# tinyusbboard_tht_singlesided.net
KiCad netlist of a schematic drawn in EAGLE
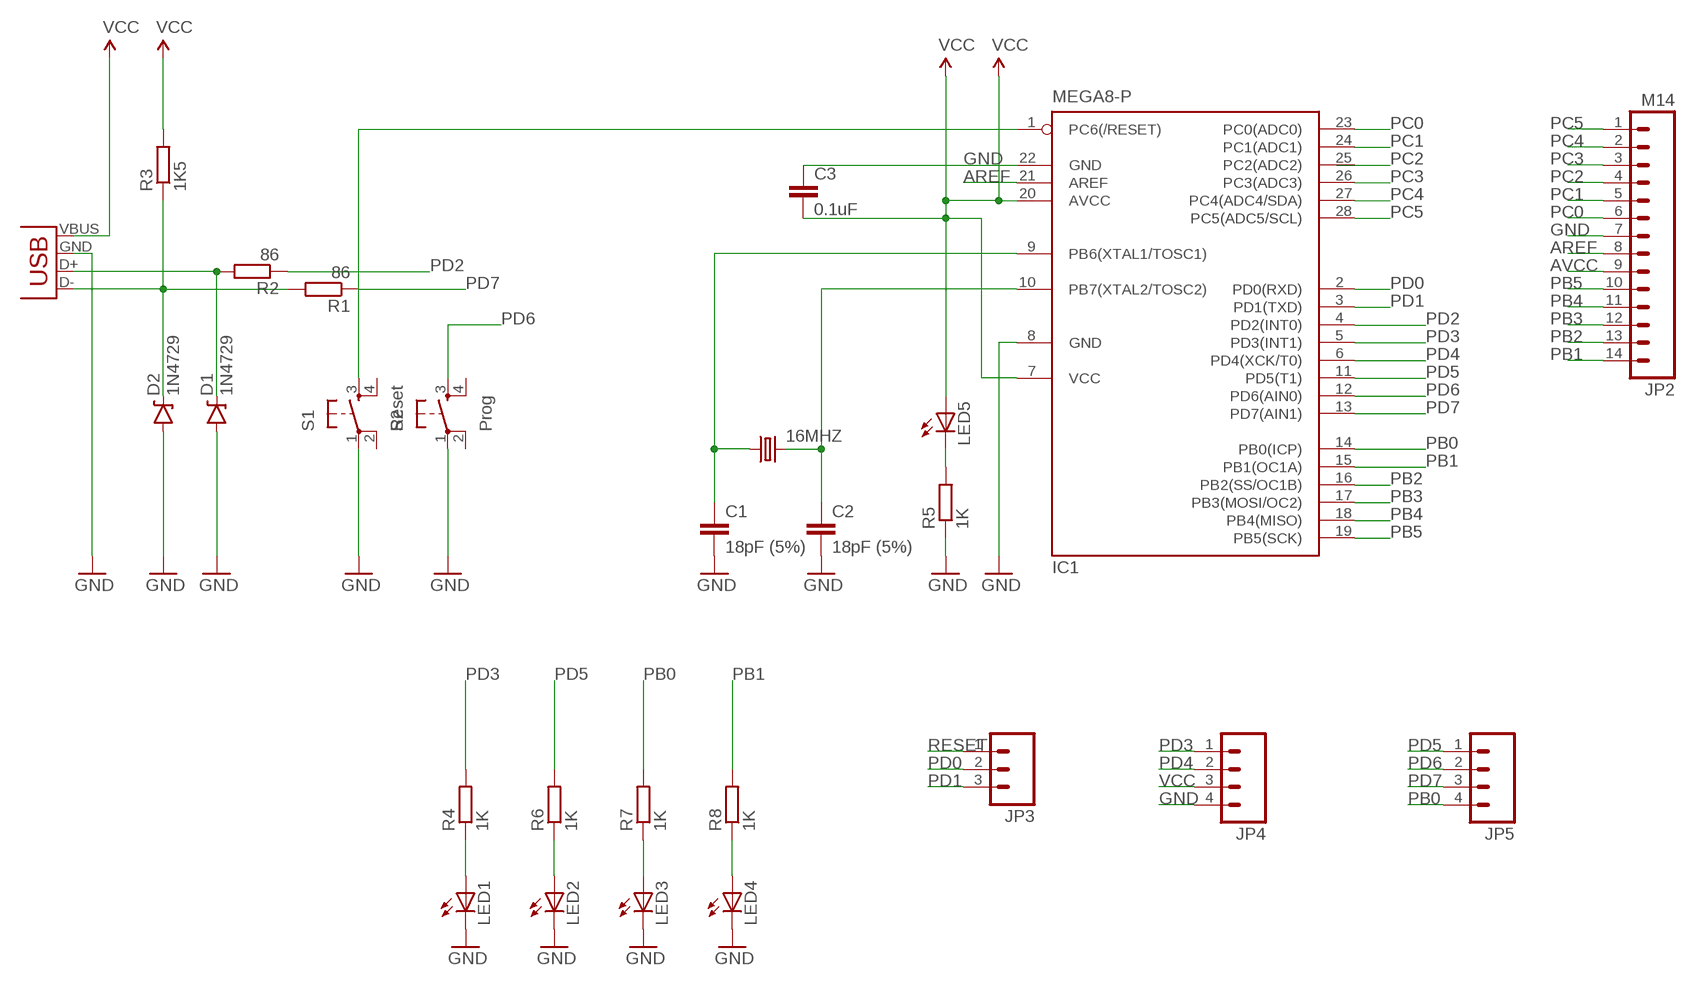
[diagram p0: schematic, sheet 1]

(export (version "E")
  (design (tool "Eeschema 10.0.6"))
  (components
    (comp (ref "16MHZ")
      (value "CRYSTALTC26V")
      (footprint "eagle-import:TC26V")
      (libsource (lib "eagle-import") (part "CRYSTALTC26V"))
    )
    (comp (ref "C1")
      (value "18pF (5%)")
      (footprint "eagle-import:C025-024X044")
      (libsource (lib "eagle-import") (part "C-EU025-024X044"))
    )
    (comp (ref "C2")
      (value "18pF (5%)")
      (footprint "eagle-import:C025-024X044")
      (libsource (lib "eagle-import") (part "C-EU025-024X044"))
    )
    (comp (ref "C3")
      (value "0.1uF")
      (footprint "eagle-import:C025-024X044")
      (libsource (lib "eagle-import") (part "C-EU025-024X044"))
    )
    (comp (ref "D1")
      (value "1N4729")
      (footprint "eagle-import:DIODE-ZENER")
      (libsource (lib "eagle-import") (part "DIODE-ZENERPTH"))
    )
    (comp (ref "D2")
      (value "1N4729")
      (footprint "eagle-import:DIODE-ZENER")
      (libsource (lib "eagle-import") (part "DIODE-ZENERPTH"))
    )
    (comp (ref "IC1")
      (value "MEGA8-P")
      (footprint "eagle-import:DIL28-3")
      (libsource (lib "eagle-import") (part "MEGA8-P"))
    )
    (comp (ref "JP1")
      (value "USB-A-H")
      (footprint "eagle-import:USB-A-H")
      (libsource (lib "eagle-import") (part "USB-A-H"))
    )
    (comp (ref "JP2")
      (value "M14")
      (footprint "eagle-import:1X14")
      (libsource (lib "eagle-import") (part "M14"))
    )
    (comp (ref "JP3")
      (value "M03PTH")
      (footprint "eagle-import:1X03")
      (libsource (lib "eagle-import") (part "M03PTH"))
    )
    (comp (ref "JP4")
      (value "M04PTH")
      (footprint "eagle-import:1X04")
      (libsource (lib "eagle-import") (part "M04PTH"))
    )
    (comp (ref "JP5")
      (value "M04PTH")
      (footprint "eagle-import:1X04")
      (libsource (lib "eagle-import") (part "M04PTH"))
    )
    (comp (ref "LED1")
      (value "LED3MM")
      (footprint "eagle-import:LED3MM")
      (libsource (lib "eagle-import") (part "LED3MM"))
    )
    (comp (ref "LED2")
      (value "LED3MM")
      (footprint "eagle-import:LED3MM")
      (libsource (lib "eagle-import") (part "LED3MM"))
    )
    (comp (ref "LED3")
      (value "LED3MM")
      (footprint "eagle-import:LED3MM")
      (libsource (lib "eagle-import") (part "LED3MM"))
    )
    (comp (ref "LED4")
      (value "LED3MM")
      (footprint "eagle-import:LED3MM")
      (libsource (lib "eagle-import") (part "LED3MM"))
    )
    (comp (ref "LED5")
      (value "LED3MM")
      (footprint "eagle-import:LED3MM")
      (libsource (lib "eagle-import") (part "LED3MM"))
    )
    (comp (ref "R1")
      (value "86")
      (footprint "eagle-import:0204_7")
      (libsource (lib "eagle-import") (part "R-EU_0204/7"))
    )
    (comp (ref "R2")
      (value "86")
      (footprint "eagle-import:0204_7")
      (libsource (lib "eagle-import") (part "R-EU_0204/7"))
    )
    (comp (ref "R3")
      (value "1K5")
      (footprint "eagle-import:0204_7")
      (libsource (lib "eagle-import") (part "R-EU_0204/7"))
    )
    (comp (ref "R4")
      (value "1K")
      (footprint "eagle-import:0204_7")
      (libsource (lib "eagle-import") (part "R-EU_0204/7"))
    )
    (comp (ref "R5")
      (value "1K")
      (footprint "eagle-import:0204_7")
      (libsource (lib "eagle-import") (part "R-EU_0204/7"))
    )
    (comp (ref "R6")
      (value "1K")
      (footprint "eagle-import:0204_7")
      (libsource (lib "eagle-import") (part "R-EU_0204/7"))
    )
    (comp (ref "R7")
      (value "1K")
      (footprint "eagle-import:0204_7")
      (libsource (lib "eagle-import") (part "R-EU_0204/7"))
    )
    (comp (ref "R8")
      (value "1K")
      (footprint "eagle-import:0204_7")
      (libsource (lib "eagle-import") (part "R-EU_0204/7"))
    )
    (comp (ref "S1")
      (value "Reset")
      (footprint "eagle-import:TACTILE-PTH")
      (libsource (lib "eagle-import") (part "TAC_SWITCHPTH"))
    )
    (comp (ref "S2")
      (value "Prog")
      (footprint "eagle-import:TACTILE-PTH")
      (libsource (lib "eagle-import") (part "TAC_SWITCHPTH"))
    )
  )
  (nets
    (net (code "1") (name "/AREF") (class "Default")
      (node (ref "IC1") (pin "21") (pinfunction "AREF_21") (pintype "passive"))
      (node (ref "JP2") (pin "8") (pinfunction "8_8") (pintype "passive"))
    )
    (net (code "2") (name "/AVCC") (class "Default")
      (node (ref "JP2") (pin "9") (pinfunction "9_9") (pintype "passive"))
    )
    (net (code "3") (name "/PB0") (class "Default")
      (node (ref "IC1") (pin "14") (pinfunction "PB0(ICP)_14") (pintype "bidirectional"))
      (node (ref "JP5") (pin "4") (pinfunction "4_4") (pintype "passive"))
      (node (ref "R7") (pin "2") (pinfunction "2_2") (pintype "passive"))
    )
    (net (code "4") (name "/PB1") (class "Default")
      (node (ref "IC1") (pin "15") (pinfunction "PB1(OC1A)_15") (pintype "bidirectional"))
      (node (ref "JP2") (pin "14") (pinfunction "14_14") (pintype "passive"))
      (node (ref "R8") (pin "2") (pinfunction "2_2") (pintype "passive"))
    )
    (net (code "5") (name "/PB2") (class "Default")
      (node (ref "IC1") (pin "16") (pinfunction "PB2(SS/OC1B)_16") (pintype "bidirectional"))
      (node (ref "JP2") (pin "13") (pinfunction "13_13") (pintype "passive"))
    )
    (net (code "6") (name "/PB3") (class "Default")
      (node (ref "IC1") (pin "17") (pinfunction "PB3(MOSI/OC2)_17") (pintype "bidirectional"))
      (node (ref "JP2") (pin "12") (pinfunction "12_12") (pintype "passive"))
    )
    (net (code "7") (name "/PB4") (class "Default")
      (node (ref "IC1") (pin "18") (pinfunction "PB4(MISO)_18") (pintype "bidirectional"))
      (node (ref "JP2") (pin "11") (pinfunction "11_11") (pintype "passive"))
    )
    (net (code "8") (name "/PB5") (class "Default")
      (node (ref "IC1") (pin "19") (pinfunction "PB5(SCK)_19") (pintype "bidirectional"))
      (node (ref "JP2") (pin "10") (pinfunction "10_10") (pintype "passive"))
    )
    (net (code "9") (name "/PC0") (class "Default")
      (node (ref "IC1") (pin "23") (pinfunction "PC0(ADC0)_23") (pintype "bidirectional"))
      (node (ref "JP2") (pin "6") (pinfunction "6_6") (pintype "passive"))
    )
    (net (code "10") (name "/PC1") (class "Default")
      (node (ref "IC1") (pin "24") (pinfunction "PC1(ADC1)_24") (pintype "bidirectional"))
      (node (ref "JP2") (pin "5") (pinfunction "5_5") (pintype "passive"))
    )
    (net (code "11") (name "/PC2") (class "Default")
      (node (ref "IC1") (pin "25") (pinfunction "PC2(ADC2)_25") (pintype "bidirectional"))
      (node (ref "JP2") (pin "4") (pinfunction "4_4") (pintype "passive"))
    )
    (net (code "12") (name "/PC3") (class "Default")
      (node (ref "IC1") (pin "26") (pinfunction "PC3(ADC3)_26") (pintype "bidirectional"))
      (node (ref "JP2") (pin "3") (pinfunction "3_3") (pintype "passive"))
    )
    (net (code "13") (name "/PC4") (class "Default")
      (node (ref "IC1") (pin "27") (pinfunction "PC4(ADC4/SDA)_27") (pintype "bidirectional"))
      (node (ref "JP2") (pin "2") (pinfunction "2_2") (pintype "passive"))
    )
    (net (code "14") (name "/PC5") (class "Default")
      (node (ref "IC1") (pin "28") (pinfunction "PC5(ADC5/SCL)_28") (pintype "bidirectional"))
      (node (ref "JP2") (pin "1") (pinfunction "1_1") (pintype "passive"))
    )
    (net (code "15") (name "/PD0") (class "Default")
      (node (ref "IC1") (pin "2") (pinfunction "PD0(RXD)_2") (pintype "bidirectional"))
      (node (ref "JP3") (pin "2") (pinfunction "2_2") (pintype "passive"))
    )
    (net (code "16") (name "/PD1") (class "Default")
      (node (ref "IC1") (pin "3") (pinfunction "PD1(TXD)_3") (pintype "bidirectional"))
      (node (ref "JP3") (pin "3") (pinfunction "3_3") (pintype "passive"))
    )
    (net (code "17") (name "/PD2") (class "Default")
      (node (ref "IC1") (pin "4") (pinfunction "PD2(INT0)_4") (pintype "bidirectional"))
      (node (ref "R2") (pin "1") (pinfunction "1_1") (pintype "passive"))
    )
    (net (code "18") (name "/PD3") (class "Default")
      (node (ref "IC1") (pin "5") (pinfunction "PD3(INT1)_5") (pintype "bidirectional"))
      (node (ref "JP4") (pin "1") (pinfunction "1_1") (pintype "passive"))
      (node (ref "R4") (pin "2") (pinfunction "2_2") (pintype "passive"))
    )
    (net (code "19") (name "/PD4") (class "Default")
      (node (ref "IC1") (pin "6") (pinfunction "PD4(XCK/T0)_6") (pintype "bidirectional"))
      (node (ref "JP4") (pin "2") (pinfunction "2_2") (pintype "passive"))
    )
    (net (code "20") (name "/PD5") (class "Default")
      (node (ref "IC1") (pin "11") (pinfunction "PD5(T1)_11") (pintype "bidirectional"))
      (node (ref "JP5") (pin "1") (pinfunction "1_1") (pintype "passive"))
      (node (ref "R6") (pin "2") (pinfunction "2_2") (pintype "passive"))
    )
    (net (code "21") (name "/PD6") (class "Default")
      (node (ref "IC1") (pin "12") (pinfunction "PD6(AIN0)_12") (pintype "bidirectional"))
      (node (ref "JP5") (pin "2") (pinfunction "2_2") (pintype "passive"))
      (node (ref "S2") (pin "3") (pinfunction "3_3") (pintype "passive"))
    )
    (net (code "22") (name "/PD7") (class "Default")
      (node (ref "IC1") (pin "13") (pinfunction "PD7(AIN1)_13") (pintype "bidirectional"))
      (node (ref "JP5") (pin "3") (pinfunction "3_3") (pintype "passive"))
      (node (ref "R1") (pin "1") (pinfunction "1_1") (pintype "passive"))
    )
    (net (code "23") (name "/RESET") (class "Default")
      (node (ref "IC1") (pin "1") (pinfunction "PC6(/RESET)_1") (pintype "bidirectional"))
      (node (ref "JP3") (pin "1") (pinfunction "1_1") (pintype "passive"))
      (node (ref "S1") (pin "3") (pinfunction "3_3") (pintype "passive"))
    )
    (net (code "24") (name "GND") (class "Default")
      (node (ref "C1") (pin "2") (pinfunction "2_2") (pintype "passive"))
      (node (ref "C2") (pin "2") (pinfunction "2_2") (pintype "passive"))
      (node (ref "C3") (pin "1") (pinfunction "1_1") (pintype "passive"))
      (node (ref "D1") (pin "P$2") (pinfunction "A_P$2") (pintype "passive"))
      (node (ref "D2") (pin "P$2") (pinfunction "A_P$2") (pintype "passive"))
      (node (ref "IC1") (pin "22") (pinfunction "GND_22") (pintype "power_in"))
      (node (ref "IC1") (pin "8") (pinfunction "GND_8") (pintype "power_in"))
      (node (ref "JP1") (pin "GND") (pinfunction "VBUS_GND") (pintype "bidirectional"))
      (node (ref "JP2") (pin "7") (pinfunction "7_7") (pintype "passive"))
      (node (ref "JP4") (pin "4") (pinfunction "4_4") (pintype "passive"))
      (node (ref "LED1") (pin "K") (pinfunction "C_K") (pintype "passive"))
      (node (ref "LED2") (pin "K") (pinfunction "C_K") (pintype "passive"))
      (node (ref "LED3") (pin "K") (pinfunction "C_K") (pintype "passive"))
      (node (ref "LED4") (pin "K") (pinfunction "C_K") (pintype "passive"))
      (node (ref "R5") (pin "1") (pinfunction "1_1") (pintype "passive"))
      (node (ref "S1") (pin "1") (pinfunction "1_1") (pintype "passive"))
      (node (ref "S2") (pin "1") (pinfunction "1_1") (pintype "passive"))
    )
    (net (code "25") (name "Net-(D1-C)") (class "Default")
      (node (ref "D1") (pin "P$1") (pinfunction "C_P$1") (pintype "passive"))
      (node (ref "JP1") (pin "D+") (pinfunction "D-_D+") (pintype "bidirectional"))
      (node (ref "R2") (pin "2") (pinfunction "2_2") (pintype "passive"))
    )
    (net (code "26") (name "Net-(D2-C)") (class "Default")
      (node (ref "D2") (pin "P$1") (pinfunction "C_P$1") (pintype "passive"))
      (node (ref "JP1") (pin "D-") (pinfunction "D+_D-") (pintype "bidirectional"))
      (node (ref "R1") (pin "2") (pinfunction "2_2") (pintype "passive"))
      (node (ref "R3") (pin "1") (pinfunction "1_1") (pintype "passive"))
    )
    (net (code "27") (name "Net-(IC1-PB6(XTAL1{slash}TOSC1))") (class "Default")
      (node (ref "16MHZ") (pin "1") (pinfunction "1_1") (pintype "passive"))
      (node (ref "C1") (pin "1") (pinfunction "1_1") (pintype "passive"))
      (node (ref "IC1") (pin "9") (pinfunction "PB6(XTAL1/TOSC1)_9") (pintype "bidirectional"))
    )
    (net (code "28") (name "Net-(IC1-PB7(XTAL2{slash}TOSC2))") (class "Default")
      (node (ref "16MHZ") (pin "2") (pinfunction "2_2") (pintype "passive"))
      (node (ref "C2") (pin "1") (pinfunction "1_1") (pintype "passive"))
      (node (ref "IC1") (pin "10") (pinfunction "PB7(XTAL2/TOSC2)_10") (pintype "bidirectional"))
    )
    (net (code "29") (name "Net-(LED1-PadA)") (class "Default")
      (node (ref "LED1") (pin "A") (pinfunction "A_A") (pintype "passive"))
      (node (ref "R4") (pin "1") (pinfunction "1_1") (pintype "passive"))
    )
    (net (code "30") (name "Net-(LED2-PadA)") (class "Default")
      (node (ref "LED2") (pin "A") (pinfunction "A_A") (pintype "passive"))
      (node (ref "R6") (pin "1") (pinfunction "1_1") (pintype "passive"))
    )
    (net (code "31") (name "Net-(LED3-PadA)") (class "Default")
      (node (ref "LED3") (pin "A") (pinfunction "A_A") (pintype "passive"))
      (node (ref "R7") (pin "1") (pinfunction "1_1") (pintype "passive"))
    )
    (net (code "32") (name "Net-(LED4-PadA)") (class "Default")
      (node (ref "LED4") (pin "A") (pinfunction "A_A") (pintype "passive"))
      (node (ref "R8") (pin "1") (pinfunction "1_1") (pintype "passive"))
    )
    (net (code "33") (name "Net-(LED5-C)") (class "Default")
      (node (ref "LED5") (pin "K") (pinfunction "C_K") (pintype "passive"))
      (node (ref "R5") (pin "2") (pinfunction "2_2") (pintype "passive"))
    )
    (net (code "34") (name "VCC") (class "Default")
      (node (ref "C3") (pin "2") (pinfunction "2_2") (pintype "passive"))
      (node (ref "IC1") (pin "20") (pinfunction "AVCC_20") (pintype "power_in"))
      (node (ref "IC1") (pin "7") (pinfunction "VCC_7") (pintype "power_in"))
      (node (ref "JP1") (pin "VBUS") (pinfunction "GND_VBUS") (pintype "bidirectional"))
      (node (ref "JP4") (pin "3") (pinfunction "3_3") (pintype "passive"))
      (node (ref "LED5") (pin "A") (pinfunction "A_A") (pintype "passive"))
      (node (ref "R3") (pin "2") (pinfunction "2_2") (pintype "passive"))
    )
    (net (code "35") (name "unconnected-(S1-Pad2)") (class "Default")
      (node (ref "S1") (pin "2") (pinfunction "2_2") (pintype "passive"))
    )
    (net (code "36") (name "unconnected-(S1-Pad4)") (class "Default")
      (node (ref "S1") (pin "4") (pinfunction "4_4") (pintype "passive"))
    )
    (net (code "37") (name "unconnected-(S2-Pad2)") (class "Default")
      (node (ref "S2") (pin "2") (pinfunction "2_2") (pintype "passive"))
    )
    (net (code "38") (name "unconnected-(S2-Pad4)") (class "Default")
      (node (ref "S2") (pin "4") (pinfunction "4_4") (pintype "passive"))
    )
  )
)
